# Main.net
KiCad netlist of a schematic drawn in Altium Designer
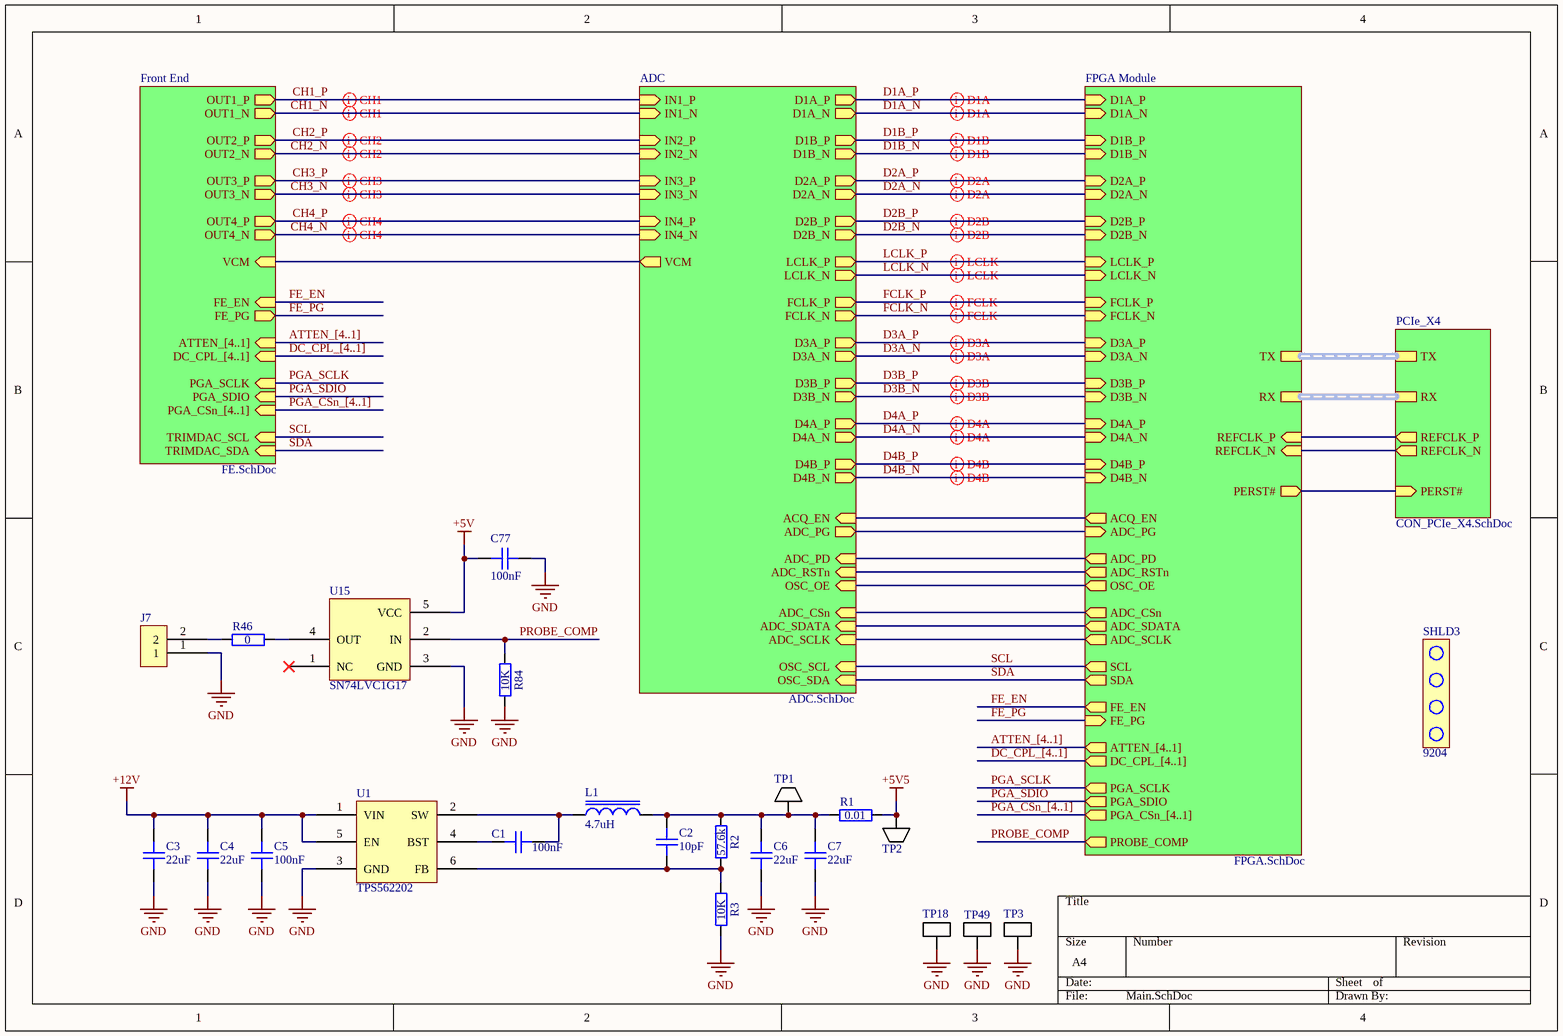
[diagram p0: Main.SchDoc]

(export (version "E")
  (design (tool "Eeschema 10.0.6"))
  (components
    (comp (ref "C1")
      (value "100nF")
      (footprint "GEN_C_0402")
      (libsource (lib "DSO") (part "CAP 100nF 16V X7R 0402"))
    )
    (comp (ref "C2")
      (value "10pF")
      (footprint "GEN_C_0402")
      (libsource (lib "DSO") (part "CAP 10pF 50V C0G 0402"))
    )
    (comp (ref "C3")
      (value "22uF")
      (footprint "GEN_C_0805")
      (libsource (lib "DSO") (part "CAP 22uF 25V X5R 0805"))
    )
    (comp (ref "C4")
      (value "22uF")
      (footprint "GEN_C_0805")
      (libsource (lib "DSO") (part "CAP 22uF 25V X5R 0805"))
    )
    (comp (ref "C5")
      (value "100nF")
      (footprint "GEN_C_0402")
      (libsource (lib "DSO") (part "CAP 100nF 16V X7R 0402"))
    )
    (comp (ref "C6")
      (value "22uF")
      (footprint "GEN_C_0805")
      (libsource (lib "DSO") (part "CAP 22uF 25V X5R 0805"))
    )
    (comp (ref "C7")
      (value "22uF")
      (footprint "GEN_C_0805")
      (libsource (lib "DSO") (part "CAP 22uF 25V X5R 0805"))
    )
    (comp (ref "C77")
      (value "100nF")
      (footprint "GEN_C_0402")
      (libsource (lib "DSO") (part "CAP 100nF 16V X7R 0402"))
    )
    (comp (ref "J7")
      (value "TSW-101-08-F-D-RA")
      (footprint "GEN_2.54mm_1x2_Pin_TH_RA")
      (libsource (lib "DSO") (part "CONN 2.54mm 2 Pin TH RA"))
    )
    (comp (ref "L1")
      (value "4.7uH")
      (footprint "TY_IND_NRS5030")
      (libsource (lib "DSO") (part "IND 4.7uH 2.6A 35 MOHM SMD"))
    )
    (comp (ref "R1")
      (value "0.01")
      (footprint "GEN_R_0603")
      (fields (field (name "TOLERANCE") "1%"))
      (libsource (lib "DSO") (part "RES 0.01 OHM 1% 1/4W 0603"))
    )
    (comp (ref "R2")
      (value "57.6k")
      (footprint "GEN_R_0402")
      (fields (field (name "TOLERANCE") "1%"))
      (libsource (lib "DSO") (part "RES 57.6K OHM 1% 1/16W 0402"))
    )
    (comp (ref "R3")
      (value "10K")
      (footprint "GEN_R_0402")
      (fields (field (name "TOLERANCE") "1%"))
      (libsource (lib "DSO") (part "RES 10K OHM 1% 1/10W 0402"))
    )
    (comp (ref "R46")
      (value "0")
      (footprint "GEN_R_0402")
      (libsource (lib "DSO") (part "RES 0 OHM 1/16W 0402"))
    )
    (comp (ref "R84")
      (value "10K")
      (footprint "GEN_R_0402")
      (fields (field (name "TOLERANCE") "1%"))
      (libsource (lib "DSO") (part "RES 10K OHM 1% 1/10W 0402"))
    )
    (comp (ref "SHLD3") (value "9204") (libsource (lib "DSO") (part "PCIe IO Shield")))
    (comp (ref "TP1") (value "5015") (footprint "KEY_5015") (libsource (lib "DSO") (part "TP KEYSTONE 5015")))
    (comp (ref "TP2") (value "5015") (footprint "KEY_5015") (libsource (lib "DSO") (part "TP KEYSTONE 5015")))
    (comp (ref "TP3") (value "5019") (footprint "KEY_5019") (libsource (lib "DSO") (part "TP KEYSTONE 5019")))
    (comp (ref "TP18")
      (value "5019")
      (footprint "KEY_5019")
      (libsource (lib "DSO") (part "TP KEYSTONE 5019"))
    )
    (comp (ref "TP49")
      (value "5019")
      (footprint "KEY_5019")
      (libsource (lib "DSO") (part "TP KEYSTONE 5019"))
    )
    (comp (ref "U1")
      (value "TPS562202")
      (footprint "TI_SOT563_DRL0006A")
      (libsource (lib "DSO") (part "IC BUCK TPS562202"))
    )
    (comp (ref "U15")
      (value "SN74LVC1G17")
      (footprint "GEN_SC-70-5")
      (libsource (lib "DSO") (part "IC BUFFER SN74LVC1G17"))
    )
  )
  (nets
    (net (code "13") (name "+5V") (class "Default")
      (node (ref "C77") (pin "1") (pinfunction "1_1") (pintype "passive"))
      (node (ref "U15") (pin "5") (pinfunction "VCC_5") (pintype "passive"))
    )
    (net (code "14") (name "+5V5") (class "Default")
      (node (ref "R1") (pin "2") (pinfunction "2_2") (pintype "passive"))
      (node (ref "TP2") (pin "1") (pinfunction "1_1") (pintype "passive"))
    )
    (net (code "15") (name "+12V") (class "Default")
      (node (ref "C3") (pin "2") (pinfunction "2_2") (pintype "passive"))
      (node (ref "C4") (pin "2") (pinfunction "2_2") (pintype "passive"))
      (node (ref "C5") (pin "1") (pinfunction "1_1") (pintype "passive"))
      (node (ref "U1") (pin "1") (pinfunction "VIN_1") (pintype "power_in"))
      (node (ref "U1") (pin "5") (pinfunction "EN_5") (pintype "passive"))
    )
    (net (code "60") (name "/PROBE_COMP") (class "Default")
      (node (ref "R84") (pin "2") (pinfunction "2_2") (pintype "passive"))
      (node (ref "U15") (pin "2") (pinfunction "IN_2") (pintype "passive"))
    )
    (net (code "68") (name "GND") (class "Default")
      (node (ref "C3") (pin "1") (pinfunction "1_1") (pintype "passive"))
      (node (ref "C4") (pin "1") (pinfunction "1_1") (pintype "passive"))
      (node (ref "C5") (pin "2") (pinfunction "2_2") (pintype "passive"))
      (node (ref "C6") (pin "1") (pinfunction "1_1") (pintype "passive"))
      (node (ref "C7") (pin "1") (pinfunction "1_1") (pintype "passive"))
      (node (ref "C77") (pin "2") (pinfunction "2_2") (pintype "passive"))
      (node (ref "J7") (pin "1") (pinfunction "1_1") (pintype "passive"))
      (node (ref "R3") (pin "1") (pinfunction "1_1") (pintype "passive"))
      (node (ref "R84") (pin "1") (pinfunction "1_1") (pintype "passive"))
      (node (ref "TP18") (pin "1") (pinfunction "1_1") (pintype "passive"))
      (node (ref "TP3") (pin "1") (pinfunction "1_1") (pintype "passive"))
      (node (ref "TP49") (pin "1") (pinfunction "1_1") (pintype "passive"))
      (node (ref "U1") (pin "3") (pinfunction "GND_3") (pintype "power_in"))
      (node (ref "U15") (pin "3") (pinfunction "GND_3") (pintype "passive"))
    )
    (net (code "69") (name "Net-(C2-Pad2)") (class "Default")
      (node (ref "C2") (pin "2") (pinfunction "2_2") (pintype "passive"))
      (node (ref "C6") (pin "2") (pinfunction "2_2") (pintype "passive"))
      (node (ref "C7") (pin "2") (pinfunction "2_2") (pintype "passive"))
      (node (ref "L1") (pin "2") (pinfunction "2_2") (pintype "passive"))
      (node (ref "R1") (pin "1") (pinfunction "1_1") (pintype "passive"))
      (node (ref "R2") (pin "2") (pinfunction "2_2") (pintype "passive"))
      (node (ref "TP1") (pin "1") (pinfunction "1_1") (pintype "passive"))
    )
    (net (code "70") (name "Net-(J7-Pad2)") (class "Default")
      (node (ref "J7") (pin "2") (pinfunction "2_2") (pintype "passive"))
      (node (ref "R46") (pin "1") (pinfunction "1_1") (pintype "passive"))
    )
    (net (code "71") (name "Net-(U1-BST)") (class "Default")
      (node (ref "C1") (pin "2") (pinfunction "2_2") (pintype "passive"))
      (node (ref "U1") (pin "4") (pinfunction "BST_4") (pintype "passive"))
    )
    (net (code "72") (name "Net-(U1-FB)") (class "Default")
      (node (ref "C2") (pin "1") (pinfunction "1_1") (pintype "passive"))
      (node (ref "R2") (pin "1") (pinfunction "1_1") (pintype "passive"))
      (node (ref "R3") (pin "2") (pinfunction "2_2") (pintype "passive"))
      (node (ref "U1") (pin "6") (pinfunction "FB_6") (pintype "passive"))
    )
    (net (code "73") (name "Net-(U1-SW)") (class "Default")
      (node (ref "C1") (pin "1") (pinfunction "1_1") (pintype "passive"))
      (node (ref "L1") (pin "1") (pinfunction "1_1") (pintype "passive"))
      (node (ref "U1") (pin "2") (pinfunction "SW_2") (pintype "passive"))
    )
    (net (code "74") (name "Net-(U15-OUT)") (class "Default")
      (node (ref "R46") (pin "2") (pinfunction "2_2") (pintype "passive"))
      (node (ref "U15") (pin "4") (pinfunction "OUT_4") (pintype "passive"))
    )
    (net (code "75") (name "unconnected-(U15-NC-Pad1)") (class "Default")
      (node (ref "U15") (pin "1") (pinfunction "NC_1") (pintype "passive+no_connect"))
    )
  )
)
